# LKS_EVB_MCU072_V1_0.net
KiCad netlist of a schematic drawn in Altium Designer
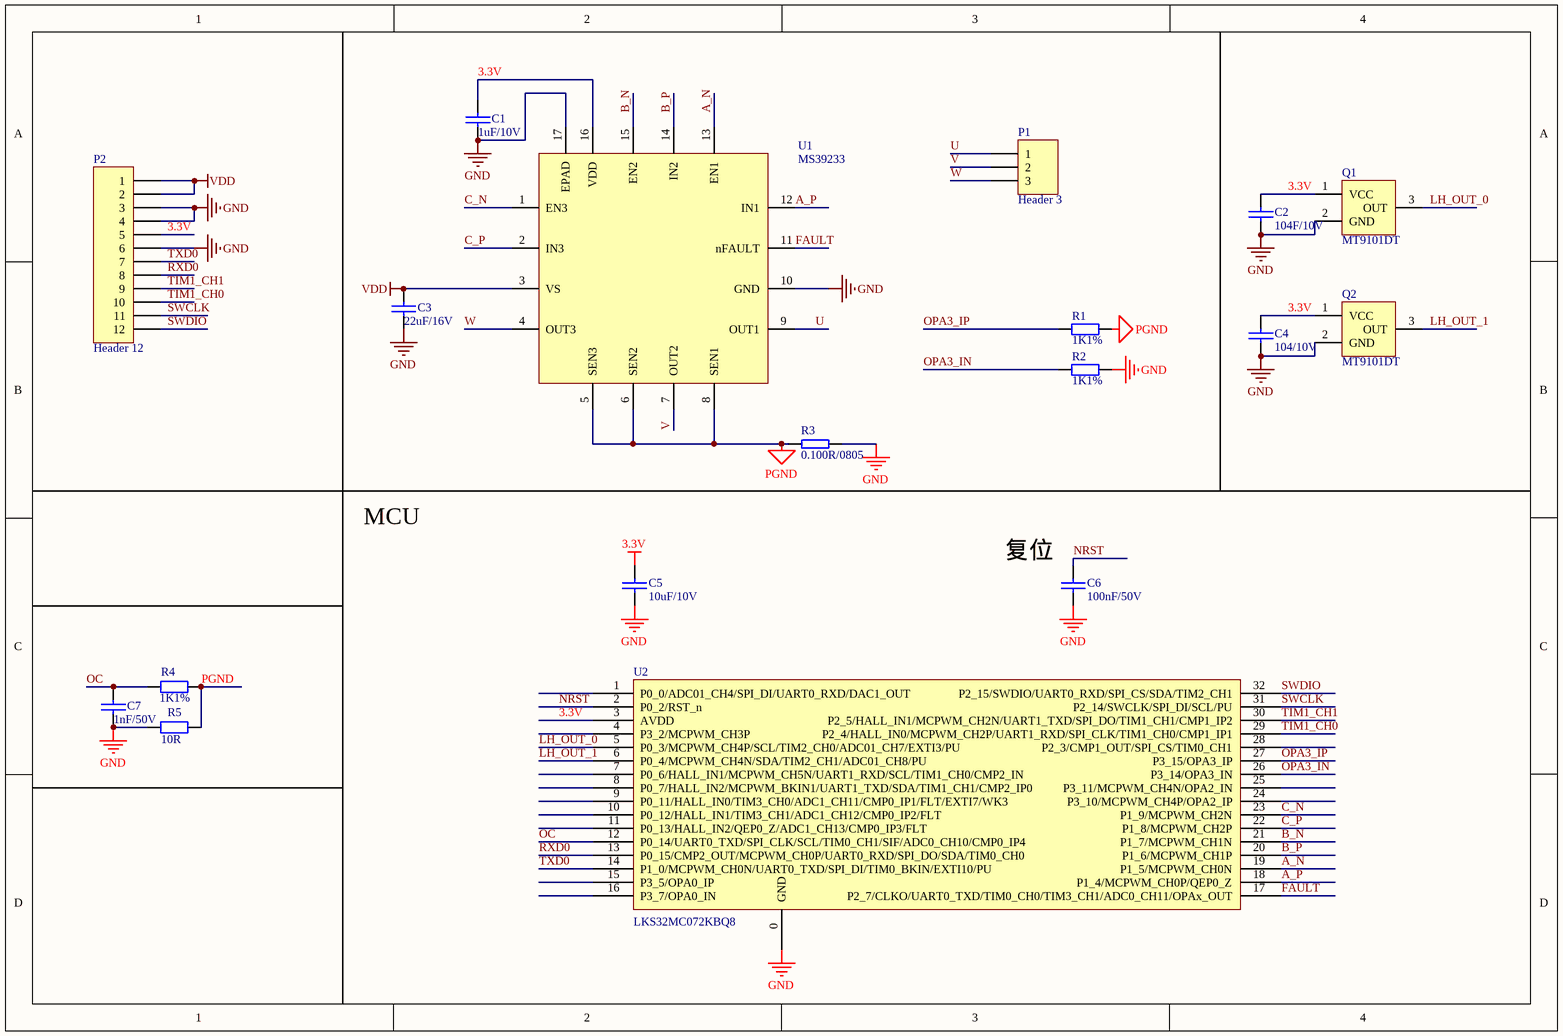
[diagram p0: LKS_EVB_MCU072_V1.0.SchDoc]

(export (version "E")
  (design (tool "Eeschema 10.0.6"))
  (components
    (comp (ref "C1")
      (value "1uF/10V")
      (footprint "C 0402_M")
      (description "Capacitor")
      (libsource (lib "*") (part "C"))
    )
    (comp (ref "C2")
      (value "104F/10V")
      (footprint "C 0402_M")
      (description "Capacitor")
      (libsource (lib "*") (part "C"))
    )
    (comp (ref "C3")
      (value "22uF/16V")
      (footprint "C 0805_M")
      (description "Capacitor")
      (libsource (lib "*") (part "C"))
    )
    (comp (ref "C4")
      (value "104/10V")
      (footprint "C 0402_M")
      (description "Capacitor")
      (libsource (lib "*") (part "C"))
    )
    (comp (ref "C5")
      (value "10uF/10V")
      (footprint "C 0402_M")
      (description "Capacitor")
      (libsource (lib "*") (part "C"))
    )
    (comp (ref "C6")
      (value "100nF/50V")
      (footprint "C 0402_M")
      (description "Capacitor")
      (libsource (lib "*") (part "C"))
    )
    (comp (ref "C7")
      (value "1nF/50V")
      (footprint "C 0402_M")
      (description "Capacitor")
      (libsource (lib "*") (part "C"))
    )
    (comp (ref "P1")
      (value "Header 3")
      (footprint "HDR1X3")
      (description "Header, 3-Pin")
      (fields (field (name "PUBLISHER") "Altium Limited"))
      (libsource (lib "Miscellaneous Connectors") (part "Header 3"))
    )
    (comp (ref "P2")
      (value "Header 12")
      (footprint "SMD-12")
      (description "Header, 12-Pin")
      (fields (field (name "PUBLISHER") "Altium Limited"))
      (libsource (lib "Miscellaneous Connectors") (part "Header 12"))
    )
    (comp (ref "Q1") (value "MT9101DT") (footprint "DFN1616") (libsource (lib "Schlib1") (part "MT9101DT")))
    (comp (ref "Q2") (value "MT9101DT") (footprint "DFN1616") (libsource (lib "Schlib1") (part "MT9101DT")))
    (comp (ref "R1")
      (value "1K1%")
      (footprint "R 0402_M")
      (description "Resistor")
      (fields (field (name "PUBLISHER") "Altium Limited"))
      (libsource (lib "LINKO_V1.0") (part "Res"))
    )
    (comp (ref "R2")
      (value "1K1%")
      (footprint "R 0402_M")
      (description "Resistor")
      (fields (field (name "PUBLISHER") "Altium Limited"))
      (libsource (lib "LINKO_V1.0") (part "Res"))
    )
    (comp (ref "R3") (value "0.100R/0805") (footprint "R 0805_M") (libsource (lib "*") (part "RES2短")))
    (comp (ref "R4")
      (value "1K1%")
      (footprint "R 0402_M")
      (description "Resistor")
      (fields (field (name "PUBLISHER") "Altium Limited"))
      (libsource (lib "") (part "Res_1"))
    )
    (comp (ref "R5")
      (value "10R")
      (footprint "R 0402_M")
      (description "Resistor")
      (fields (field (name "PUBLISHER") "Altium Limited"))
      (libsource (lib "LINKO_V1.0") (part "Res"))
    )
    (comp (ref "U1") (value "MS39233") (footprint "QFN16") (libsource (lib "Schlib1") (part "MS39233")))
    (comp (ref "U2")
      (value "LKS32MC072KBQ8")
      (footprint "QFN32 5x5_M")
      (description "LKS32MC072KBQ8\r\n凌鸥创芯，128KFlash，12KRAM")
      (libsource (lib "LINKO_V1.1") (part "LKS32MC072KBQ82"))
    )
  )
  (nets
    (net (code "1") (name "/A_N") (class "Default")
      (node (ref "U1") (pin "13") (pinfunction "EN1_13") (pintype "passive"))
      (node (ref "U2") (pin "19") (pinfunction "P1_5/MCPWM_CH0N_19") (pintype "passive"))
    )
    (net (code "2") (name "/A_P") (class "Default")
      (node (ref "U1") (pin "12") (pinfunction "IN1_12") (pintype "passive"))
      (node (ref "U2") (pin "18") (pinfunction "P1_4/MCPWM_CH0P/QEP0_Z_18") (pintype "passive"))
    )
    (net (code "3") (name "/B_N") (class "Default")
      (node (ref "U1") (pin "15") (pinfunction "EN2_15") (pintype "passive"))
      (node (ref "U2") (pin "21") (pinfunction "P1_7/MCPWM_CH1N_21") (pintype "passive"))
    )
    (net (code "4") (name "/B_P") (class "Default")
      (node (ref "U1") (pin "14") (pinfunction "IN2_14") (pintype "passive"))
      (node (ref "U2") (pin "20") (pinfunction "P1_6/MCPWM_CH1P_20") (pintype "passive"))
    )
    (net (code "5") (name "/C_N") (class "Default")
      (node (ref "U1") (pin "1") (pinfunction "EN3_1") (pintype "passive"))
      (node (ref "U2") (pin "23") (pinfunction "P1_9/MCPWM_CH2N_23") (pintype "passive"))
    )
    (net (code "6") (name "/C_P") (class "Default")
      (node (ref "U1") (pin "2") (pinfunction "IN3_2") (pintype "passive"))
      (node (ref "U2") (pin "22") (pinfunction "P1_8/MCPWM_CH2P_22") (pintype "passive"))
    )
    (net (code "7") (name "/FAULT") (class "Default")
      (node (ref "U1") (pin "11") (pinfunction "nFAULT_11") (pintype "passive"))
      (node (ref "U2") (pin "17") (pinfunction "P2_7/CLKO/UART0_TXD/TIM0_CH0/TIM3_CH1/ADC0_CH11/OPAx_OUT_17") (pintype "passive"))
    )
    (net (code "8") (name "/LH_OUT_0") (class "Default")
      (node (ref "Q1") (pin "3") (pinfunction "OUT_3") (pintype "passive"))
      (node (ref "U2") (pin "5") (pinfunction "P0_3/MCPWM_CH4P/SCL/TIM2_CH0/ADC01_CH7/EXTI3/PU_5") (pintype "passive"))
    )
    (net (code "9") (name "/LH_OUT_1") (class "Default")
      (node (ref "Q2") (pin "3") (pinfunction "OUT_3") (pintype "passive"))
      (node (ref "U2") (pin "6") (pinfunction "P0_4/MCPWM_CH4N/SDA/TIM2_CH1/ADC01_CH8/PU_6") (pintype "passive"))
    )
    (net (code "10") (name "/NRST") (class "Default")
      (node (ref "C6") (pin "1") (pinfunction "1_1") (pintype "passive"))
      (node (ref "U2") (pin "2") (pinfunction "P0_2/RST_n_2") (pintype "passive"))
    )
    (net (code "11") (name "/OC") (class "Default")
      (node (ref "C7") (pin "2") (pinfunction "2_2") (pintype "passive"))
      (node (ref "R4") (pin "1") (pinfunction "1_1") (pintype "passive"))
      (node (ref "U2") (pin "12") (pinfunction "P0_14/UART0_TXD/SPI_CLK/SCL/TIM0_CH1/SIF/ADC0_CH10/CMP0_IP4_12") (pintype "passive"))
    )
    (net (code "12") (name "/OPA3_IN") (class "Default")
      (node (ref "R2") (pin "2") (pinfunction "2_2") (pintype "passive"))
      (node (ref "U2") (pin "26") (pinfunction "P3_14/OPA3_IN_26") (pintype "passive"))
    )
    (net (code "13") (name "/OPA3_IP") (class "Default")
      (node (ref "R1") (pin "2") (pinfunction "2_2") (pintype "passive"))
      (node (ref "U2") (pin "27") (pinfunction "P3_15/OPA3_IP_27") (pintype "passive"))
    )
    (net (code "14") (name "/RXD0") (class "Default")
      (node (ref "P2") (pin "8") (pinfunction "8_8") (pintype "passive"))
      (node (ref "U2") (pin "13") (pinfunction "P0_15/CMP2_OUT/MCPWM_CH0P/UART0_RXD/SPI_DO/SDA/TIM0_CH0_13") (pintype "passive"))
    )
    (net (code "15") (name "/SWCLK") (class "Default")
      (node (ref "P2") (pin "11") (pinfunction "11_11") (pintype "passive"))
      (node (ref "U2") (pin "31") (pinfunction "P2_14/SWCLK/SPI_DI/SCL/PU_31") (pintype "passive"))
    )
    (net (code "16") (name "/SWDIO") (class "Default")
      (node (ref "P2") (pin "12") (pinfunction "12_12") (pintype "passive"))
      (node (ref "U2") (pin "32") (pinfunction "P2_15/SWDIO/UART0_RXD/SPI_CS/SDA/TIM2_CH1_32") (pintype "passive"))
    )
    (net (code "17") (name "/TIM1_CH0") (class "Default")
      (node (ref "P2") (pin "10") (pinfunction "10_10") (pintype "passive"))
      (node (ref "U2") (pin "29") (pinfunction "P2_4/HALL_IN0/MCPWM_CH2P/UART1_RXD/SPI_CLK/TIM1_CH0/CMP1_IP1_29") (pintype "passive"))
    )
    (net (code "18") (name "/TIM1_CH1") (class "Default")
      (node (ref "P2") (pin "9") (pinfunction "9_9") (pintype "passive"))
      (node (ref "U2") (pin "30") (pinfunction "P2_5/HALL_IN1/MCPWM_CH2N/UART1_TXD/SPI_DO/TIM1_CH1/CMP1_IP2_30") (pintype "passive"))
    )
    (net (code "19") (name "/TXD0") (class "Default")
      (node (ref "P2") (pin "7") (pinfunction "7_7") (pintype "passive"))
      (node (ref "U2") (pin "14") (pinfunction "P1_0/MCPWM_CH0N/UART0_TXD/SPI_DI/TIM0_BKIN/EXTI10/PU_14") (pintype "passive"))
    )
    (net (code "20") (name "/U") (class "Default")
      (node (ref "P1") (pin "1") (pinfunction "1_1") (pintype "passive"))
      (node (ref "U1") (pin "9") (pinfunction "OUT1_9") (pintype "passive"))
    )
    (net (code "21") (name "/V") (class "Default")
      (node (ref "P1") (pin "2") (pinfunction "2_2") (pintype "passive"))
      (node (ref "U1") (pin "7") (pinfunction "OUT2_7") (pintype "passive"))
    )
    (net (code "22") (name "/W") (class "Default")
      (node (ref "P1") (pin "3") (pinfunction "3_3") (pintype "passive"))
      (node (ref "U1") (pin "4") (pinfunction "OUT3_4") (pintype "passive"))
    )
    (net (code "23") (name "3.3V") (class "Default")
      (node (ref "C1") (pin "2") (pinfunction "2_2") (pintype "passive"))
      (node (ref "C2") (pin "2") (pinfunction "2_2") (pintype "passive"))
      (node (ref "C4") (pin "2") (pinfunction "2_2") (pintype "passive"))
      (node (ref "C5") (pin "2") (pinfunction "2_2") (pintype "passive"))
      (node (ref "P2") (pin "5") (pinfunction "5_5") (pintype "passive"))
      (node (ref "Q1") (pin "1") (pinfunction "VCC_1") (pintype "passive"))
      (node (ref "Q2") (pin "1") (pinfunction "VCC_1") (pintype "passive"))
      (node (ref "U1") (pin "16") (pinfunction "VDD_16") (pintype "passive"))
      (node (ref "U2") (pin "3") (pinfunction "AVDD_3") (pintype "passive"))
    )
    (net (code "24") (name "GND") (class "Default")
      (node (ref "C1") (pin "1") (pinfunction "1_1") (pintype "passive"))
      (node (ref "C2") (pin "1") (pinfunction "1_1") (pintype "passive"))
      (node (ref "C3") (pin "1") (pinfunction "1_1") (pintype "passive"))
      (node (ref "C4") (pin "1") (pinfunction "1_1") (pintype "passive"))
      (node (ref "C5") (pin "1") (pinfunction "1_1") (pintype "passive"))
      (node (ref "C6") (pin "2") (pinfunction "2_2") (pintype "passive"))
      (node (ref "C7") (pin "1") (pinfunction "1_1") (pintype "passive"))
      (node (ref "P2") (pin "3") (pinfunction "3_3") (pintype "passive"))
      (node (ref "P2") (pin "4") (pinfunction "4_4") (pintype "passive"))
      (node (ref "P2") (pin "6") (pinfunction "6_6") (pintype "passive"))
      (node (ref "Q1") (pin "2") (pinfunction "GND_2") (pintype "passive"))
      (node (ref "Q2") (pin "2") (pinfunction "GND_2") (pintype "passive"))
      (node (ref "R2") (pin "1") (pinfunction "1_1") (pintype "passive"))
      (node (ref "R3") (pin "2") (pinfunction "2_2") (pintype "passive"))
      (node (ref "R5") (pin "2") (pinfunction "2_2") (pintype "passive"))
      (node (ref "U1") (pin "10") (pinfunction "GND_10") (pintype "passive"))
      (node (ref "U1") (pin "17") (pinfunction "EPAD_17") (pintype "passive"))
      (node (ref "U2") (pin "0") (pinfunction "GND_0") (pintype "passive"))
    )
    (net (code "25") (name "PGND") (class "Default")
      (node (ref "R1") (pin "1") (pinfunction "1_1") (pintype "passive"))
      (node (ref "R3") (pin "1") (pinfunction "1_1") (pintype "passive"))
      (node (ref "R4") (pin "2") (pinfunction "2_2") (pintype "passive"))
      (node (ref "R5") (pin "1") (pinfunction "1_1") (pintype "passive"))
      (node (ref "U1") (pin "5") (pinfunction "SEN3_5") (pintype "passive"))
      (node (ref "U1") (pin "6") (pinfunction "SEN2_6") (pintype "passive"))
      (node (ref "U1") (pin "8") (pinfunction "SEN1_8") (pintype "passive"))
    )
    (net (code "26") (name "VDD") (class "Default")
      (node (ref "C3") (pin "2") (pinfunction "2_2") (pintype "passive"))
      (node (ref "P2") (pin "1") (pinfunction "1_1") (pintype "passive"))
      (node (ref "P2") (pin "2") (pinfunction "2_2") (pintype "passive"))
      (node (ref "U1") (pin "3") (pinfunction "VS_3") (pintype "passive"))
    )
    (net (code "27") (name "unconnected-(U2-P0_0{slash}ADC01_CH4{slash}SPI_DI{slash}UART0_RXD{slash}DAC1_OUT-Pad1)") (class "Default")
      (node (ref "U2") (pin "1") (pinfunction "P0_0/ADC01_CH4/SPI_DI/UART0_RXD/DAC1_OUT_1") (pintype "passive"))
    )
    (net (code "28") (name "unconnected-(U2-P0_6{slash}HALL_IN1{slash}MCPWM_CH5N{slash}UART1_RXD{slash}SCL{slash}TIM1_CH0{slash}CMP2_IN-Pad7)") (class "Default")
      (node (ref "U2") (pin "7") (pinfunction "P0_6/HALL_IN1/MCPWM_CH5N/UART1_RXD/SCL/TIM1_CH0/CMP2_IN_7") (pintype "passive"))
    )
    (net (code "29") (name "unconnected-(U2-P0_7{slash}HALL_IN2{slash}MCPWM_BKIN1{slash}UART1_TXD{slash}SDA{slash}TIM1_CH1{slash}CMP2_IP0-Pad8)") (class "Default")
      (node (ref "U2") (pin "8") (pinfunction "P0_7/HALL_IN2/MCPWM_BKIN1/UART1_TXD/SDA/TIM1_CH1/CMP2_IP0_8") (pintype "passive"))
    )
    (net (code "30") (name "unconnected-(U2-P0_11{slash}HALL_IN0{slash}TIM3_CH0{slash}ADC1_CH11{slash}CMP0_IP1{slash}FLT{slash}EXTI7{slash}WK3-Pad9)") (class "Default")
      (node (ref "U2") (pin "9") (pinfunction "P0_11/HALL_IN0/TIM3_CH0/ADC1_CH11/CMP0_IP1/FLT/EXTI7/WK3_9") (pintype "passive"))
    )
    (net (code "31") (name "unconnected-(U2-P0_12{slash}HALL_IN1{slash}TIM3_CH1{slash}ADC1_CH12{slash}CMP0_IP2{slash}FLT-Pad10)") (class "Default")
      (node (ref "U2") (pin "10") (pinfunction "P0_12/HALL_IN1/TIM3_CH1/ADC1_CH12/CMP0_IP2/FLT_10") (pintype "passive"))
    )
    (net (code "32") (name "unconnected-(U2-P0_13{slash}HALL_IN2{slash}QEP0_Z{slash}ADC1_CH13{slash}CMP0_IP3{slash}FLT-Pad11)") (class "Default")
      (node (ref "U2") (pin "11") (pinfunction "P0_13/HALL_IN2/QEP0_Z/ADC1_CH13/CMP0_IP3/FLT_11") (pintype "passive"))
    )
    (net (code "33") (name "unconnected-(U2-P2_3{slash}CMP1_OUT{slash}SPI_CS{slash}TIM0_CH1-Pad28)") (class "Default")
      (node (ref "U2") (pin "28") (pinfunction "P2_3/CMP1_OUT/SPI_CS/TIM0_CH1_28") (pintype "passive"))
    )
    (net (code "34") (name "unconnected-(U2-P3_2{slash}MCPWM_CH3P-Pad4)") (class "Default")
      (node (ref "U2") (pin "4") (pinfunction "P3_2/MCPWM_CH3P_4") (pintype "passive"))
    )
    (net (code "35") (name "unconnected-(U2-P3_5{slash}OPA0_IP-Pad15)") (class "Default")
      (node (ref "U2") (pin "15") (pinfunction "P3_5/OPA0_IP_15") (pintype "passive"))
    )
    (net (code "36") (name "unconnected-(U2-P3_7{slash}OPA0_IN-Pad16)") (class "Default")
      (node (ref "U2") (pin "16") (pinfunction "P3_7/OPA0_IN_16") (pintype "passive"))
    )
    (net (code "37") (name "unconnected-(U2-P3_10{slash}MCPWM_CH4P{slash}OPA2_IP-Pad24)") (class "Default")
      (node (ref "U2") (pin "24") (pinfunction "P3_10/MCPWM_CH4P/OPA2_IP_24") (pintype "passive"))
    )
    (net (code "38") (name "unconnected-(U2-P3_11{slash}MCPWM_CH4N{slash}OPA2_IN-Pad25)") (class "Default")
      (node (ref "U2") (pin "25") (pinfunction "P3_11/MCPWM_CH4N/OPA2_IN_25") (pintype "passive"))
    )
  )
)
